# Raihansyah_A_M_21507334077_schematic_mea.net
KiCad netlist of a schematic drawn in EAGLE
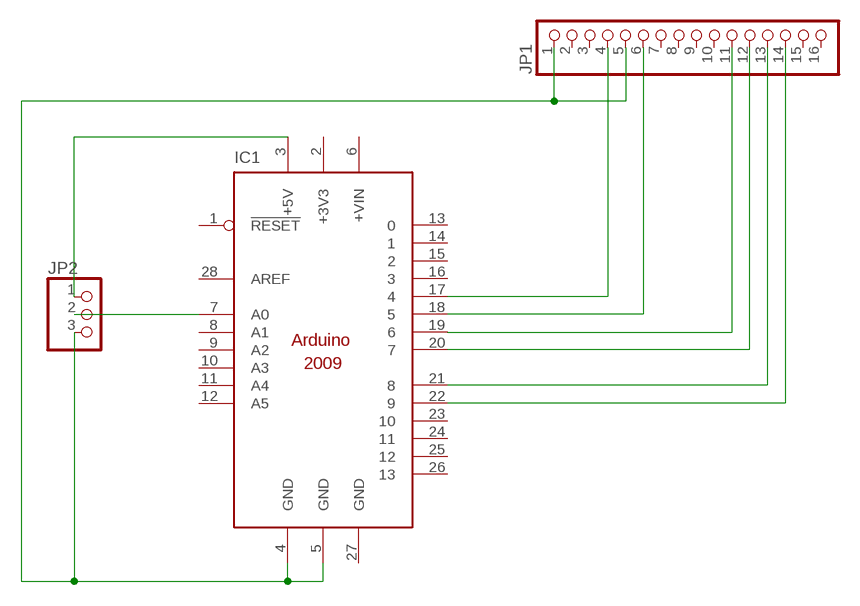
[diagram p0: schematic, sheet 1]

(export (version "E")
  (design (tool "Eeschema 10.0.6"))
  (components
    (comp (ref "IC1")
      (value "ARDUINO2009_12")
      (footprint "eagle-import:ARDUINO2009_2")
      (libsource (lib "eagle-import") (part "ARDUINO2009_12"))
    )
    (comp (ref "JP1")
      (value "PINHD-1X16")
      (footprint "eagle-import:1X16")
      (libsource (lib "eagle-import") (part "PINHD-1X16"))
    )
    (comp (ref "JP2")
      (value "PINHD-1X3")
      (footprint "eagle-import:1X03")
      (libsource (lib "eagle-import") (part "PINHD-1X3"))
    )
  )
  (nets
    (net (code "1") (name "/+3V3") (class "Default")
      (node (ref "IC1") (pin "2") (pinfunction "+3V3_2") (pintype "power_in"))
    )
    (net (code "2") (name "/GND") (class "Default")
      (node (ref "IC1") (pin "27") (pinfunction "GND_27") (pintype "power_in"))
    )
    (net (code "3") (name "Net-(IC1-+5V)") (class "Default")
      (node (ref "IC1") (pin "3") (pinfunction "+5V_3") (pintype "power_in"))
      (node (ref "JP2") (pin "1") (pinfunction "1_1") (pintype "passive"))
    )
    (net (code "4") (name "Net-(IC1-4)") (class "Default")
      (node (ref "IC1") (pin "17") (pinfunction "4_17") (pintype "bidirectional"))
      (node (ref "JP1") (pin "4") (pinfunction "4_4") (pintype "passive"))
    )
    (net (code "5") (name "Net-(IC1-5)") (class "Default")
      (node (ref "IC1") (pin "18") (pinfunction "5_18") (pintype "bidirectional"))
      (node (ref "JP1") (pin "6") (pinfunction "6_6") (pintype "passive"))
    )
    (net (code "6") (name "Net-(IC1-6)") (class "Default")
      (node (ref "IC1") (pin "19") (pinfunction "6_19") (pintype "bidirectional"))
      (node (ref "JP1") (pin "11") (pinfunction "11_11") (pintype "passive"))
    )
    (net (code "7") (name "Net-(IC1-7)") (class "Default")
      (node (ref "IC1") (pin "20") (pinfunction "7_20") (pintype "bidirectional"))
      (node (ref "JP1") (pin "12") (pinfunction "12_12") (pintype "passive"))
    )
    (net (code "8") (name "Net-(IC1-8)") (class "Default")
      (node (ref "IC1") (pin "21") (pinfunction "8_21") (pintype "bidirectional"))
      (node (ref "JP1") (pin "13") (pinfunction "13_13") (pintype "passive"))
    )
    (net (code "9") (name "Net-(IC1-9)") (class "Default")
      (node (ref "IC1") (pin "22") (pinfunction "9_22") (pintype "bidirectional"))
      (node (ref "JP1") (pin "14") (pinfunction "14_14") (pintype "passive"))
    )
    (net (code "10") (name "Net-(IC1-A0)") (class "Default")
      (node (ref "IC1") (pin "7") (pinfunction "A0_7") (pintype "bidirectional"))
      (node (ref "JP2") (pin "2") (pinfunction "2_2") (pintype "passive"))
    )
    (net (code "11") (name "Net-(IC1-GND-Pad4)") (class "Default")
      (node (ref "IC1") (pin "4") (pinfunction "GND_4") (pintype "power_in"))
      (node (ref "IC1") (pin "5") (pinfunction "GND_5") (pintype "power_in"))
      (node (ref "JP1") (pin "1") (pinfunction "1_1") (pintype "passive"))
      (node (ref "JP1") (pin "5") (pinfunction "5_5") (pintype "passive"))
      (node (ref "JP2") (pin "3") (pinfunction "3_3") (pintype "passive"))
    )
    (net (code "12") (name "unconnected-(IC1-+VIN-Pad6)") (class "Default")
      (node (ref "IC1") (pin "6") (pinfunction "+VIN_6") (pintype "bidirectional"))
    )
    (net (code "13") (name "unconnected-(IC1-0-Pad13)") (class "Default")
      (node (ref "IC1") (pin "13") (pinfunction "0_13") (pintype "bidirectional"))
    )
    (net (code "14") (name "unconnected-(IC1-1-Pad14)") (class "Default")
      (node (ref "IC1") (pin "14") (pinfunction "1_14") (pintype "bidirectional"))
    )
    (net (code "15") (name "unconnected-(IC1-2-Pad15)") (class "Default")
      (node (ref "IC1") (pin "15") (pinfunction "2_15") (pintype "bidirectional"))
    )
    (net (code "16") (name "unconnected-(IC1-3-Pad16)") (class "Default")
      (node (ref "IC1") (pin "16") (pinfunction "3_16") (pintype "bidirectional"))
    )
    (net (code "17") (name "unconnected-(IC1-10-Pad23)") (class "Default")
      (node (ref "IC1") (pin "23") (pinfunction "10_23") (pintype "bidirectional"))
    )
    (net (code "18") (name "unconnected-(IC1-11-Pad24)") (class "Default")
      (node (ref "IC1") (pin "24") (pinfunction "11_24") (pintype "bidirectional"))
    )
    (net (code "19") (name "unconnected-(IC1-12-Pad25)") (class "Default")
      (node (ref "IC1") (pin "25") (pinfunction "12_25") (pintype "bidirectional"))
    )
    (net (code "20") (name "unconnected-(IC1-13-Pad26)") (class "Default")
      (node (ref "IC1") (pin "26") (pinfunction "13_26") (pintype "bidirectional"))
    )
    (net (code "21") (name "unconnected-(IC1-A1-Pad8)") (class "Default")
      (node (ref "IC1") (pin "8") (pinfunction "A1_8") (pintype "bidirectional"))
    )
    (net (code "22") (name "unconnected-(IC1-A2-Pad9)") (class "Default")
      (node (ref "IC1") (pin "9") (pinfunction "A2_9") (pintype "bidirectional"))
    )
    (net (code "23") (name "unconnected-(IC1-A3-Pad10)") (class "Default")
      (node (ref "IC1") (pin "10") (pinfunction "A3_10") (pintype "bidirectional"))
    )
    (net (code "24") (name "unconnected-(IC1-A4-Pad11)") (class "Default")
      (node (ref "IC1") (pin "11") (pinfunction "A4_11") (pintype "bidirectional"))
    )
    (net (code "25") (name "unconnected-(IC1-A5-Pad12)") (class "Default")
      (node (ref "IC1") (pin "12") (pinfunction "A5_12") (pintype "bidirectional"))
    )
    (net (code "26") (name "unconnected-(IC1-AREF-Pad28)") (class "Default")
      (node (ref "IC1") (pin "28") (pinfunction "AREF_28") (pintype "bidirectional"))
    )
    (net (code "27") (name "unconnected-(IC1-~{RESET}-Pad1)") (class "Default")
      (node (ref "IC1") (pin "1") (pinfunction "~{RESET}_1") (pintype "bidirectional"))
    )
    (net (code "28") (name "unconnected-(JP1-Pad2)") (class "Default")
      (node (ref "JP1") (pin "2") (pinfunction "2_2") (pintype "passive"))
    )
    (net (code "29") (name "unconnected-(JP1-Pad3)") (class "Default")
      (node (ref "JP1") (pin "3") (pinfunction "3_3") (pintype "passive"))
    )
    (net (code "30") (name "unconnected-(JP1-Pad7)") (class "Default")
      (node (ref "JP1") (pin "7") (pinfunction "7_7") (pintype "passive"))
    )
    (net (code "31") (name "unconnected-(JP1-Pad8)") (class "Default")
      (node (ref "JP1") (pin "8") (pinfunction "8_8") (pintype "passive"))
    )
    (net (code "32") (name "unconnected-(JP1-Pad9)") (class "Default")
      (node (ref "JP1") (pin "9") (pinfunction "9_9") (pintype "passive"))
    )
    (net (code "33") (name "unconnected-(JP1-Pad10)") (class "Default")
      (node (ref "JP1") (pin "10") (pinfunction "10_10") (pintype "passive"))
    )
    (net (code "34") (name "unconnected-(JP1-Pad15)") (class "Default")
      (node (ref "JP1") (pin "15") (pinfunction "15_15") (pintype "passive"))
    )
    (net (code "35") (name "unconnected-(JP1-Pad16)") (class "Default")
      (node (ref "JP1") (pin "16") (pinfunction "16_16") (pintype "passive"))
    )
  )
)
